# Impedance_7x7.net
KiCad netlist of a schematic drawn in EAGLE
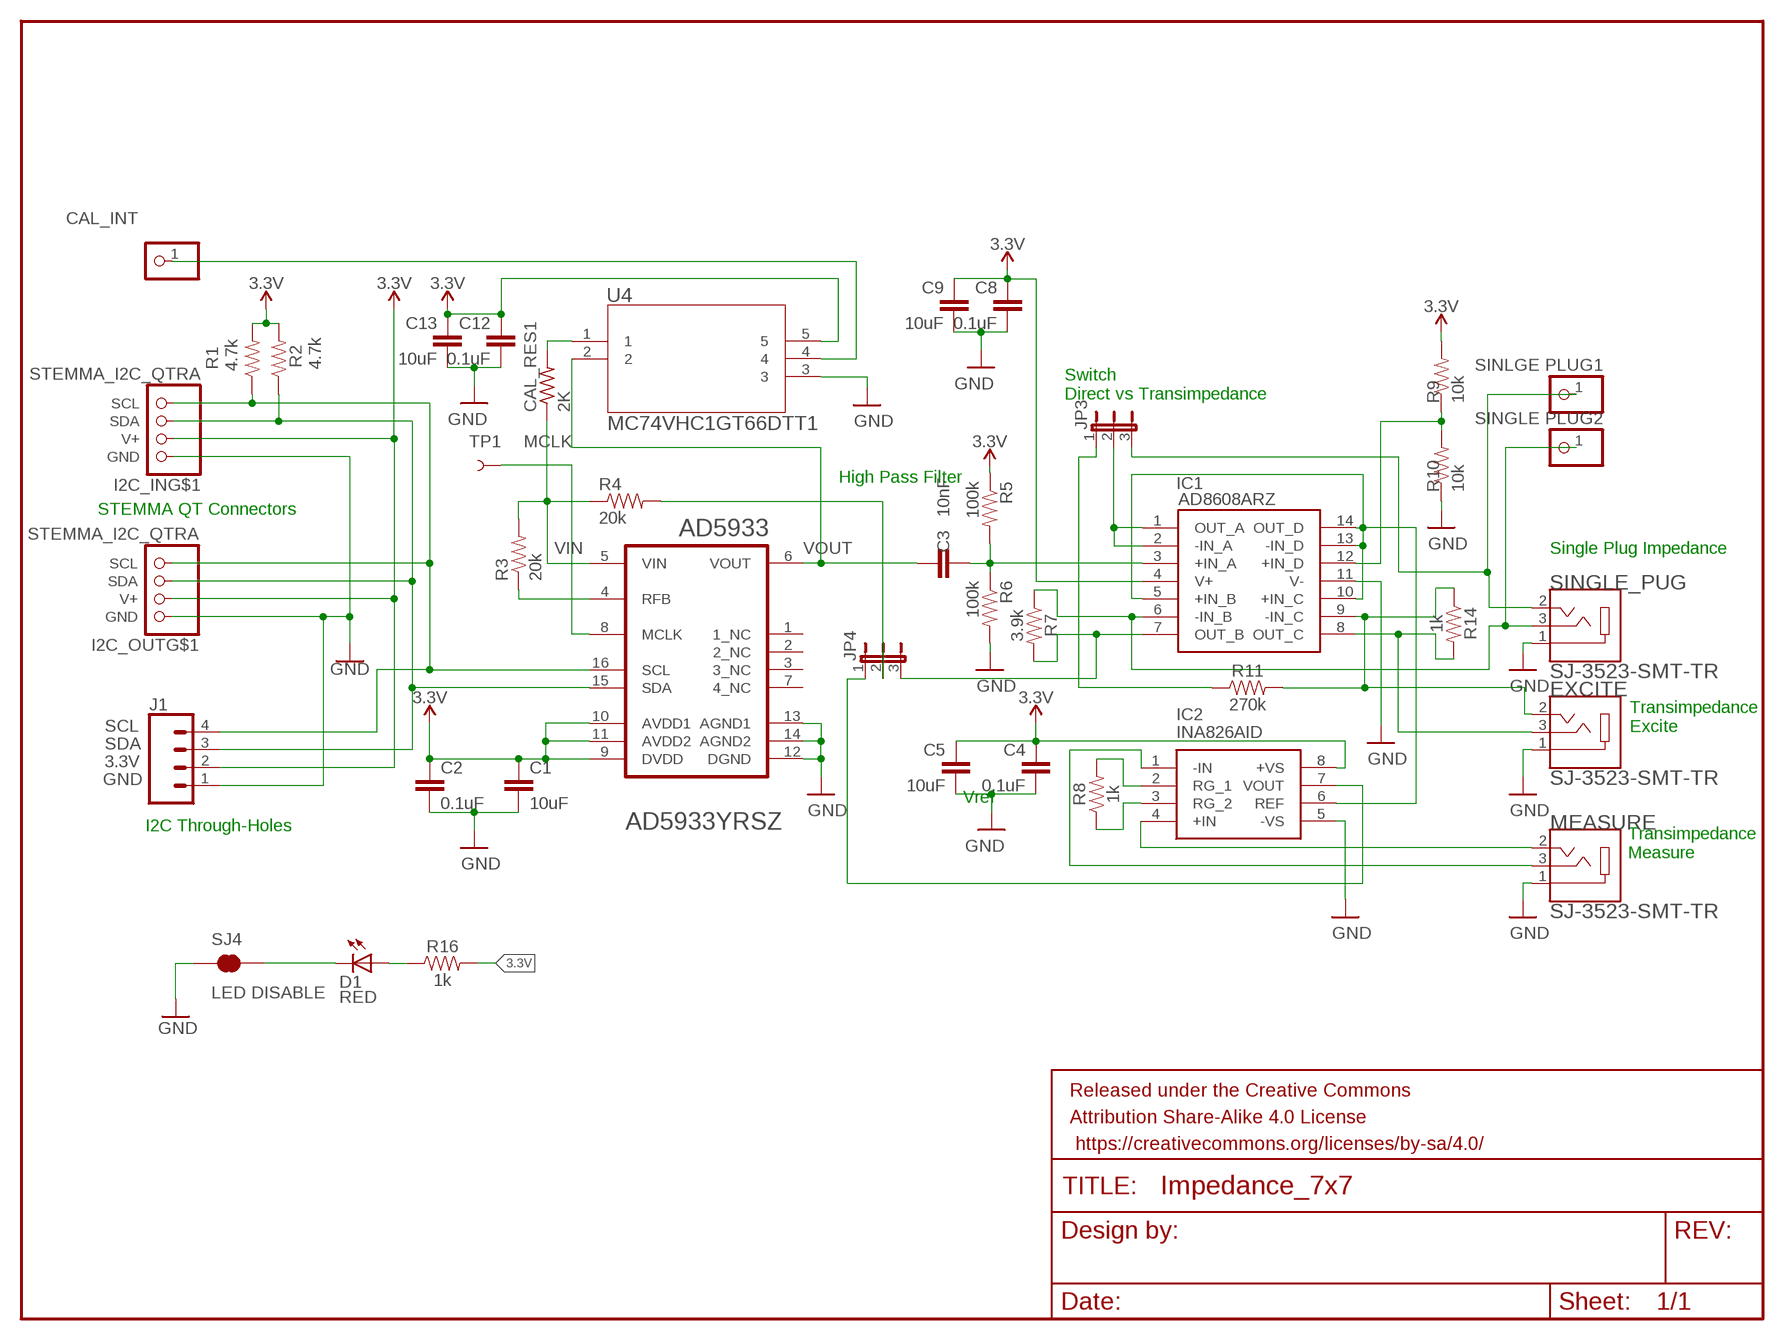
[diagram p0: schematic, sheet 1]

(export (version "E")
  (design (tool "Eeschema 10.0.6"))
  (components
    (comp (ref "AD5933")
      (value "ANALOG_DEVICES_AD5933YRSZANALOG_DEVICES_AD5933YRSZ_0_0")
      (footprint "eagle-import:ANALOG_DEVICES_AD5933YRSZ_0")
      (fields (field (name "MF") "Analog Devices") (field (name "MPN") "AD5933YRSZ"))
      (libsource (lib "eagle-import") (part "ANALOG_DEVICES_AD5933YRSZANALOG_DEVICES_AD5933YRSZ_0_0"))
    )
    (comp (ref "C1")
      (value "10uF")
      (footprint "eagle-import:C0603")
      (libsource (lib "eagle-import") (part "C-EUC0603"))
    )
    (comp (ref "C2")
      (value "0.1uF")
      (footprint "eagle-import:C0603")
      (libsource (lib "eagle-import") (part "C-EUC0603"))
    )
    (comp (ref "C3")
      (value "10nF")
      (footprint "eagle-import:0603")
      (libsource (lib "eagle-import") (part "0.1UF-0603-25V-(+80/-20%)"))
    )
    (comp (ref "C4")
      (value "0.1uF")
      (footprint "eagle-import:C0603")
      (libsource (lib "eagle-import") (part "C-EUC0603"))
    )
    (comp (ref "C5")
      (value "10uF")
      (footprint "eagle-import:C0603")
      (libsource (lib "eagle-import") (part "C-EUC0603"))
    )
    (comp (ref "C8")
      (value "0.1uF")
      (footprint "eagle-import:C0603")
      (libsource (lib "eagle-import") (part "C-EUC0603"))
    )
    (comp (ref "C9")
      (value "10uF")
      (footprint "eagle-import:C0603")
      (libsource (lib "eagle-import") (part "C-EUC0603"))
    )
    (comp (ref "C12")
      (value "0.1uF")
      (footprint "eagle-import:C0603")
      (libsource (lib "eagle-import") (part "C-EUC0603"))
    )
    (comp (ref "C13")
      (value "10uF")
      (footprint "eagle-import:C0603")
      (libsource (lib "eagle-import") (part "C-EUC0603"))
    )
    (comp (ref "CAL_INT")
      (value "PINHD-1X1")
      (footprint "eagle-import:1X01")
      (libsource (lib "eagle-import") (part "PINHD-1X1"))
    )
    (comp (ref "CAL_RES1")
      (value "2K")
      (footprint "eagle-import:R0603")
      (libsource (lib "eagle-import") (part "R-US_R0603"))
    )
    (comp (ref "D1")
      (value "RED")
      (footprint "eagle-import:LED-0603")
      (libsource (lib "eagle-import") (part "LED-RED0603"))
    )
    (comp (ref "EXCITE")
      (value "SJ-3523-SMT-TR")
      (footprint "eagle-import:CUI_SJ-3523-SMT-TR")
      (fields (field (name "MF") "CUI Devices"))
      (libsource (lib "eagle-import") (part "SJ-3523-SMT-TR"))
    )
    (comp (ref "FRAME1")
      (value "FRAME-LETTERNO_PACKAGE")
      (footprint "eagle-import:DUMMY")
      (fields (field (name "DESIGNER") "Nobody"))
      (libsource (lib "eagle-import") (part "FRAME-LETTERNO_PACKAGE"))
    )
    (comp (ref "I2C_IN")
      (value "STEMMA_I2C_QTRA")
      (footprint "eagle-import:JST_SH4_RA")
      (libsource (lib "eagle-import") (part "STEMMA_I2C_QTRA"))
    )
    (comp (ref "I2C_OUT")
      (value "STEMMA_I2C_QTRA")
      (footprint "eagle-import:JST_SH4_RA")
      (libsource (lib "eagle-import") (part "STEMMA_I2C_QTRA"))
    )
    (comp (ref "IC1")
      (value "AD8608ARZ")
      (footprint "eagle-import:SOIC127P600X175-14N")
      (fields (field (name "MOUSER_PART_NUMBER") "584-AD8608ARZ"))
      (libsource (lib "eagle-import") (part "AD8608ARZ"))
    )
    (comp (ref "IC2")
      (value "INA826AID")
      (footprint "eagle-import:SOIC127P600X175-8N")
      (fields (field (name "MOUSER_PART_NUMBER") "595-INA826AID"))
      (libsource (lib "eagle-import") (part "INA826AID"))
    )
    (comp (ref "J1")
      (value "CONN_04")
      (footprint "eagle-import:1X04")
      (libsource (lib "eagle-import") (part "CONN_04"))
    )
    (comp (ref "JP3")
      (value "JP2E")
      (footprint "eagle-import:JP2")
      (libsource (lib "eagle-import") (part "JP2E"))
    )
    (comp (ref "JP4")
      (value "JP2E")
      (footprint "eagle-import:JP2")
      (libsource (lib "eagle-import") (part "JP2E"))
    )
    (comp (ref "MEASURE")
      (value "SJ-3523-SMT-TR")
      (footprint "eagle-import:CUI_SJ-3523-SMT-TR")
      (fields (field (name "MF") "CUI Devices"))
      (libsource (lib "eagle-import") (part "SJ-3523-SMT-TR"))
    )
    (comp (ref "R1")
      (value "4.7k")
      (footprint "eagle-import:0603")
      (libsource (lib "eagle-import") (part "4.7KOHM-0603-1/10W-1%"))
    )
    (comp (ref "R2")
      (value "4.7k")
      (footprint "eagle-import:0603")
      (libsource (lib "eagle-import") (part "4.7KOHM-0603-1/10W-1%"))
    )
    (comp (ref "R3")
      (value "20k")
      (footprint "eagle-import:0603")
      (libsource (lib "eagle-import") (part "20KOHM-0603-1/10W-1%"))
    )
    (comp (ref "R4")
      (value "20k")
      (footprint "eagle-import:0603")
      (libsource (lib "eagle-import") (part "20KOHM-0603-1/10W-1%"))
    )
    (comp (ref "R5")
      (value "100k")
      (footprint "eagle-import:0603")
      (libsource (lib "eagle-import") (part "47KOHM-0603-1/10W-1%"))
    )
    (comp (ref "R6")
      (value "100k")
      (footprint "eagle-import:0603")
      (libsource (lib "eagle-import") (part "47KOHM-0603-1/10W-1%"))
    )
    (comp (ref "R7")
      (value "3.9k")
      (footprint "eagle-import:0603")
      (libsource (lib "eagle-import") (part "3.9KOHM-0603-1/10W-1%"))
    )
    (comp (ref "R8")
      (value "1k")
      (footprint "eagle-import:0603")
      (libsource (lib "eagle-import") (part "5.6KOHM-0603-1/10W-1%"))
    )
    (comp (ref "R9")
      (value "10k")
      (footprint "eagle-import:0603")
      (libsource (lib "eagle-import") (part "47KOHM-0603-1/10W-1%"))
    )
    (comp (ref "R10")
      (value "10k")
      (footprint "eagle-import:0603")
      (libsource (lib "eagle-import") (part "47KOHM-0603-1/10W-1%"))
    )
    (comp (ref "R11")
      (value "270k")
      (footprint "eagle-import:0603")
      (libsource (lib "eagle-import") (part "1KOHM-0603-1/10W-1%"))
    )
    (comp (ref "R14")
      (value "1k")
      (footprint "eagle-import:0603")
      (libsource (lib "eagle-import") (part "1KOHM-0603-1/10W-1%"))
    )
    (comp (ref "R16")
      (value "1k")
      (footprint "eagle-import:0603")
      (libsource (lib "eagle-import") (part "1KOHM-0603-1/10W-1%"))
    )
    (comp (ref "SINGLE_PLUG1")
      (value "SINLGE PLUG1")
      (footprint "eagle-import:1X01")
      (libsource (lib "eagle-import") (part "PINHD-1X1"))
    )
    (comp (ref "SINGLE_PLUG2")
      (value "SINGLE PLUG2")
      (footprint "eagle-import:1X01")
      (libsource (lib "eagle-import") (part "PINHD-1X1"))
    )
    (comp (ref "SINGLE_PUG")
      (value "SJ-3523-SMT-TR")
      (footprint "eagle-import:CUI_SJ-3523-SMT-TR")
      (fields (field (name "MF") "CUI Devices"))
      (libsource (lib "eagle-import") (part "SJ-3523-SMT-TR"))
    )
    (comp (ref "SJ4")
      (value "LED DISABLE")
      (footprint "eagle-import:SMT-JUMPER_2_NC_TRACE_NO-SILK")
      (libsource (lib "eagle-import") (part "JUMPER-SMT_2_NC_TRACE_NO-SILK"))
    )
    (comp (ref "TP1")
      (value "TEST-POINT3X5")
      (footprint "eagle-import:PAD.03X.05")
      (libsource (lib "eagle-import") (part "TEST-POINT3X5"))
    )
    (comp (ref "U4")
      (value "MC74VHC1GT66DTT1")
      (footprint "eagle-import:TSOP5_1P65X3P15_ONS")
      (fields (field (name "COPYRIGHT") "Copyright (C) 2024 Ultra Librarian. All rights reserved."))
      (libsource (lib "eagle-import") (part "MC74VHC1GT66DTT1"))
    )
  )
  (nets
    (net (code "1") (name "/MCLK") (class "Default")
      (node (ref "AD5933") (pin "8") (pinfunction "MCLK_8") (pintype "input"))
      (node (ref "TP1") (pin "P$1") (pinfunction "1_P$1") (pintype "bidirectional"))
    )
    (net (code "2") (name "/SCL") (class "Default")
      (node (ref "AD5933") (pin "16") (pinfunction "SCL_16") (pintype "input"))
      (node (ref "I2C_IN") (pin "4") (pinfunction "SCL_4") (pintype "passive"))
      (node (ref "I2C_OUT") (pin "4") (pinfunction "SCL_4") (pintype "passive"))
      (node (ref "J1") (pin "4") (pinfunction "4_4") (pintype "passive"))
      (node (ref "R1") (pin "1") (pinfunction "1_1") (pintype "passive"))
    )
    (net (code "3") (name "/SDA") (class "Default")
      (node (ref "AD5933") (pin "15") (pinfunction "SDA_15") (pintype "bidirectional"))
      (node (ref "I2C_IN") (pin "3") (pinfunction "SDA_3") (pintype "passive"))
      (node (ref "I2C_OUT") (pin "3") (pinfunction "SDA_3") (pintype "passive"))
      (node (ref "J1") (pin "3") (pinfunction "3_3") (pintype "passive"))
      (node (ref "R2") (pin "1") (pinfunction "1_1") (pintype "passive"))
    )
    (net (code "4") (name "/VIN") (class "Default")
      (node (ref "AD5933") (pin "5") (pinfunction "VIN_5") (pintype "input"))
      (node (ref "CAL_RES1") (pin "1") (pinfunction "1_1") (pintype "passive"))
      (node (ref "R3") (pin "2") (pinfunction "2_2") (pintype "passive"))
      (node (ref "R4") (pin "1") (pinfunction "1_1") (pintype "passive"))
    )
    (net (code "5") (name "/VOUT") (class "Default")
      (node (ref "AD5933") (pin "6") (pinfunction "VOUT_6") (pintype "output"))
      (node (ref "C3") (pin "1") (pinfunction "1_1") (pintype "passive"))
      (node (ref "U4") (pin "2") (pinfunction "2_2") (pintype "passive"))
    )
    (net (code "6") (name "3.3V") (class "Default")
      (node (ref "AD5933") (pin "10") (pinfunction "AVDD1_10") (pintype "power_in"))
      (node (ref "AD5933") (pin "11") (pinfunction "AVDD2_11") (pintype "power_in"))
      (node (ref "AD5933") (pin "9") (pinfunction "DVDD_9") (pintype "power_in"))
      (node (ref "C1") (pin "1") (pinfunction "1_1") (pintype "passive"))
      (node (ref "C12") (pin "1") (pinfunction "1_1") (pintype "passive"))
      (node (ref "C13") (pin "1") (pinfunction "1_1") (pintype "passive"))
      (node (ref "C2") (pin "1") (pinfunction "1_1") (pintype "passive"))
      (node (ref "C4") (pin "1") (pinfunction "1_1") (pintype "passive"))
      (node (ref "C5") (pin "1") (pinfunction "1_1") (pintype "passive"))
      (node (ref "C8") (pin "1") (pinfunction "1_1") (pintype "passive"))
      (node (ref "C9") (pin "1") (pinfunction "1_1") (pintype "passive"))
      (node (ref "I2C_IN") (pin "2") (pinfunction "V+_2") (pintype "passive"))
      (node (ref "I2C_OUT") (pin "2") (pinfunction "V+_2") (pintype "passive"))
      (node (ref "IC1") (pin "4") (pinfunction "V+_4") (pintype "power_in"))
      (node (ref "IC2") (pin "8") (pinfunction "+VS_8") (pintype "bidirectional"))
      (node (ref "J1") (pin "2") (pinfunction "2_2") (pintype "passive"))
      (node (ref "R1") (pin "2") (pinfunction "2_2") (pintype "passive"))
      (node (ref "R16") (pin "2") (pinfunction "2_2") (pintype "passive"))
      (node (ref "R2") (pin "2") (pinfunction "2_2") (pintype "passive"))
      (node (ref "R5") (pin "1") (pinfunction "1_1") (pintype "passive"))
      (node (ref "R9") (pin "2") (pinfunction "2_2") (pintype "passive"))
      (node (ref "U4") (pin "5") (pinfunction "5_5") (pintype "passive"))
    )
    (net (code "7") (name "GND") (class "Default")
      (node (ref "AD5933") (pin "12") (pinfunction "DGND_12") (pintype "power_in"))
      (node (ref "AD5933") (pin "13") (pinfunction "AGND1_13") (pintype "power_in"))
      (node (ref "AD5933") (pin "14") (pinfunction "AGND2_14") (pintype "power_in"))
      (node (ref "C1") (pin "2") (pinfunction "2_2") (pintype "passive"))
      (node (ref "C12") (pin "2") (pinfunction "2_2") (pintype "passive"))
      (node (ref "C13") (pin "2") (pinfunction "2_2") (pintype "passive"))
      (node (ref "C2") (pin "2") (pinfunction "2_2") (pintype "passive"))
      (node (ref "C4") (pin "2") (pinfunction "2_2") (pintype "passive"))
      (node (ref "C5") (pin "2") (pinfunction "2_2") (pintype "passive"))
      (node (ref "C8") (pin "2") (pinfunction "2_2") (pintype "passive"))
      (node (ref "C9") (pin "2") (pinfunction "2_2") (pintype "passive"))
      (node (ref "EXCITE") (pin "1") (pinfunction "1_1") (pintype "passive"))
      (node (ref "I2C_IN") (pin "1") (pinfunction "GND_1") (pintype "passive"))
      (node (ref "I2C_OUT") (pin "1") (pinfunction "GND_1") (pintype "passive"))
      (node (ref "IC1") (pin "11") (pinfunction "V-_11") (pintype "power_in"))
      (node (ref "IC2") (pin "5") (pinfunction "-VS_5") (pintype "bidirectional"))
      (node (ref "J1") (pin "1") (pinfunction "1_1") (pintype "passive"))
      (node (ref "MEASURE") (pin "1") (pinfunction "1_1") (pintype "passive"))
      (node (ref "R10") (pin "1") (pinfunction "1_1") (pintype "passive"))
      (node (ref "R6") (pin "2") (pinfunction "2_2") (pintype "passive"))
      (node (ref "SINGLE_PUG") (pin "1") (pinfunction "1_1") (pintype "passive"))
      (node (ref "SJ4") (pin "1") (pinfunction "1_1") (pintype "passive"))
      (node (ref "U4") (pin "3") (pinfunction "3_3") (pintype "passive"))
    )
    (net (code "8") (name "Net-(AD5933-RFB)") (class "Default")
      (node (ref "AD5933") (pin "4") (pinfunction "RFB_4") (pintype "input"))
      (node (ref "R3") (pin "1") (pinfunction "1_1") (pintype "passive"))
    )
    (net (code "9") (name "Net-(CAL_INT-Pad1)") (class "Default")
      (node (ref "CAL_INT") (pin "1") (pinfunction "1_1") (pintype "passive"))
      (node (ref "U4") (pin "4") (pinfunction "4_4") (pintype "passive"))
    )
    (net (code "10") (name "Net-(CAL_RES1-Pad2)") (class "Default")
      (node (ref "CAL_RES1") (pin "2") (pinfunction "2_2") (pintype "passive"))
      (node (ref "U4") (pin "1") (pinfunction "1_1") (pintype "passive"))
    )
    (net (code "11") (name "Net-(D1-PadA)") (class "Default")
      (node (ref "D1") (pin "A") (pinfunction "A_A") (pintype "passive"))
      (node (ref "R16") (pin "1") (pinfunction "1_1") (pintype "passive"))
    )
    (net (code "12") (name "Net-(D1-PadC)") (class "Default")
      (node (ref "D1") (pin "C") (pinfunction "C_C") (pintype "passive"))
      (node (ref "SJ4") (pin "2") (pinfunction "2_2") (pintype "passive"))
    )
    (net (code "13") (name "Net-(IC1-+IN_A)") (class "Default")
      (node (ref "C3") (pin "2") (pinfunction "2_2") (pintype "passive"))
      (node (ref "IC1") (pin "3") (pinfunction "+IN_A_3") (pintype "input"))
      (node (ref "R5") (pin "2") (pinfunction "2_2") (pintype "passive"))
      (node (ref "R6") (pin "1") (pinfunction "1_1") (pintype "passive"))
    )
    (net (code "14") (name "Net-(IC1-+IN_B)") (class "Default")
      (node (ref "IC1") (pin "10") (pinfunction "+IN_C_10") (pintype "input"))
      (node (ref "IC1") (pin "13") (pinfunction "-IN_D_13") (pintype "input"))
      (node (ref "IC1") (pin "14") (pinfunction "OUT_D_14") (pintype "output"))
      (node (ref "IC1") (pin "5") (pinfunction "+IN_B_5") (pintype "input"))
      (node (ref "IC2") (pin "6") (pinfunction "REF_6") (pintype "bidirectional"))
    )
    (net (code "15") (name "Net-(IC1-+IN_D)") (class "Default")
      (node (ref "IC1") (pin "12") (pinfunction "+IN_D_12") (pintype "input"))
      (node (ref "R10") (pin "2") (pinfunction "2_2") (pintype "passive"))
      (node (ref "R9") (pin "1") (pinfunction "1_1") (pintype "passive"))
    )
    (net (code "16") (name "Net-(IC1--IN_A)") (class "Default")
      (node (ref "IC1") (pin "1") (pinfunction "OUT_A_1") (pintype "output"))
      (node (ref "IC1") (pin "2") (pinfunction "-IN_A_2") (pintype "input"))
      (node (ref "JP3") (pin "2") (pinfunction "2_2") (pintype "passive"))
    )
    (net (code "17") (name "Net-(IC1--IN_B)") (class "Default")
      (node (ref "IC1") (pin "6") (pinfunction "-IN_B_6") (pintype "input"))
      (node (ref "R7") (pin "1") (pinfunction "1_1") (pintype "passive"))
      (node (ref "SINGLE_PLUG2") (pin "1") (pinfunction "1_1") (pintype "passive"))
      (node (ref "SINGLE_PUG") (pin "3") (pinfunction "3_3") (pintype "passive"))
    )
    (net (code "18") (name "Net-(IC1--IN_C)") (class "Default")
      (node (ref "EXCITE") (pin "2") (pinfunction "2_2") (pintype "passive"))
      (node (ref "IC1") (pin "9") (pinfunction "-IN_C_9") (pintype "input"))
      (node (ref "R11") (pin "2") (pinfunction "2_2") (pintype "passive"))
      (node (ref "R14") (pin "1") (pinfunction "1_1") (pintype "passive"))
    )
    (net (code "19") (name "Net-(IC1-OUT_B)") (class "Default")
      (node (ref "IC1") (pin "7") (pinfunction "OUT_B_7") (pintype "output"))
      (node (ref "JP4") (pin "3") (pinfunction "3_3") (pintype "passive"))
      (node (ref "R7") (pin "2") (pinfunction "2_2") (pintype "passive"))
    )
    (net (code "20") (name "Net-(IC1-OUT_C)") (class "Default")
      (node (ref "EXCITE") (pin "3") (pinfunction "3_3") (pintype "passive"))
      (node (ref "IC1") (pin "8") (pinfunction "OUT_C_8") (pintype "output"))
      (node (ref "R14") (pin "2") (pinfunction "2_2") (pintype "passive"))
    )
    (net (code "21") (name "Net-(IC2-+IN)") (class "Default")
      (node (ref "IC2") (pin "4") (pinfunction "+IN_4") (pintype "bidirectional"))
      (node (ref "MEASURE") (pin "2") (pinfunction "2_2") (pintype "passive"))
    )
    (net (code "22") (name "Net-(IC2--IN)") (class "Default")
      (node (ref "IC2") (pin "1") (pinfunction "-IN_1") (pintype "bidirectional"))
      (node (ref "MEASURE") (pin "3") (pinfunction "3_3") (pintype "passive"))
    )
    (net (code "23") (name "Net-(IC2-RG_1)") (class "Default")
      (node (ref "IC2") (pin "2") (pinfunction "RG_1_2") (pintype "bidirectional"))
      (node (ref "R8") (pin "2") (pinfunction "2_2") (pintype "passive"))
    )
    (net (code "24") (name "Net-(IC2-RG_2)") (class "Default")
      (node (ref "IC2") (pin "3") (pinfunction "RG_2_3") (pintype "bidirectional"))
      (node (ref "R8") (pin "1") (pinfunction "1_1") (pintype "passive"))
    )
    (net (code "25") (name "Net-(IC2-VOUT)") (class "Default")
      (node (ref "IC2") (pin "7") (pinfunction "VOUT_7") (pintype "bidirectional"))
      (node (ref "JP4") (pin "1") (pinfunction "1_1") (pintype "passive"))
    )
    (net (code "26") (name "Net-(JP3-Pad1)") (class "Default")
      (node (ref "JP3") (pin "1") (pinfunction "1_1") (pintype "passive"))
      (node (ref "R11") (pin "1") (pinfunction "1_1") (pintype "passive"))
    )
    (net (code "27") (name "Net-(JP3-Pad3)") (class "Default")
      (node (ref "JP3") (pin "3") (pinfunction "3_3") (pintype "passive"))
      (node (ref "SINGLE_PLUG1") (pin "1") (pinfunction "1_1") (pintype "passive"))
      (node (ref "SINGLE_PUG") (pin "2") (pinfunction "2_2") (pintype "passive"))
    )
    (net (code "28") (name "Net-(JP4-Pad2)") (class "Default")
      (node (ref "JP4") (pin "2") (pinfunction "2_2") (pintype "passive"))
      (node (ref "R4") (pin "2") (pinfunction "2_2") (pintype "passive"))
    )
    (net (code "29") (name "unconnected-(AD5933-1_NC-Pad1)") (class "Default")
      (node (ref "AD5933") (pin "1") (pinfunction "1_NC_1") (pintype "passive"))
    )
    (net (code "30") (name "unconnected-(AD5933-2_NC-Pad2)") (class "Default")
      (node (ref "AD5933") (pin "2") (pinfunction "2_NC_2") (pintype "passive"))
    )
    (net (code "31") (name "unconnected-(AD5933-3_NC-Pad3)") (class "Default")
      (node (ref "AD5933") (pin "3") (pinfunction "3_NC_3") (pintype "passive"))
    )
    (net (code "32") (name "unconnected-(AD5933-4_NC-Pad7)") (class "Default")
      (node (ref "AD5933") (pin "7") (pinfunction "4_NC_7") (pintype "passive"))
    )
  )
)
